# STM32FOC_AD_SCH.net
KiCad netlist of a schematic drawn in Altium Designer
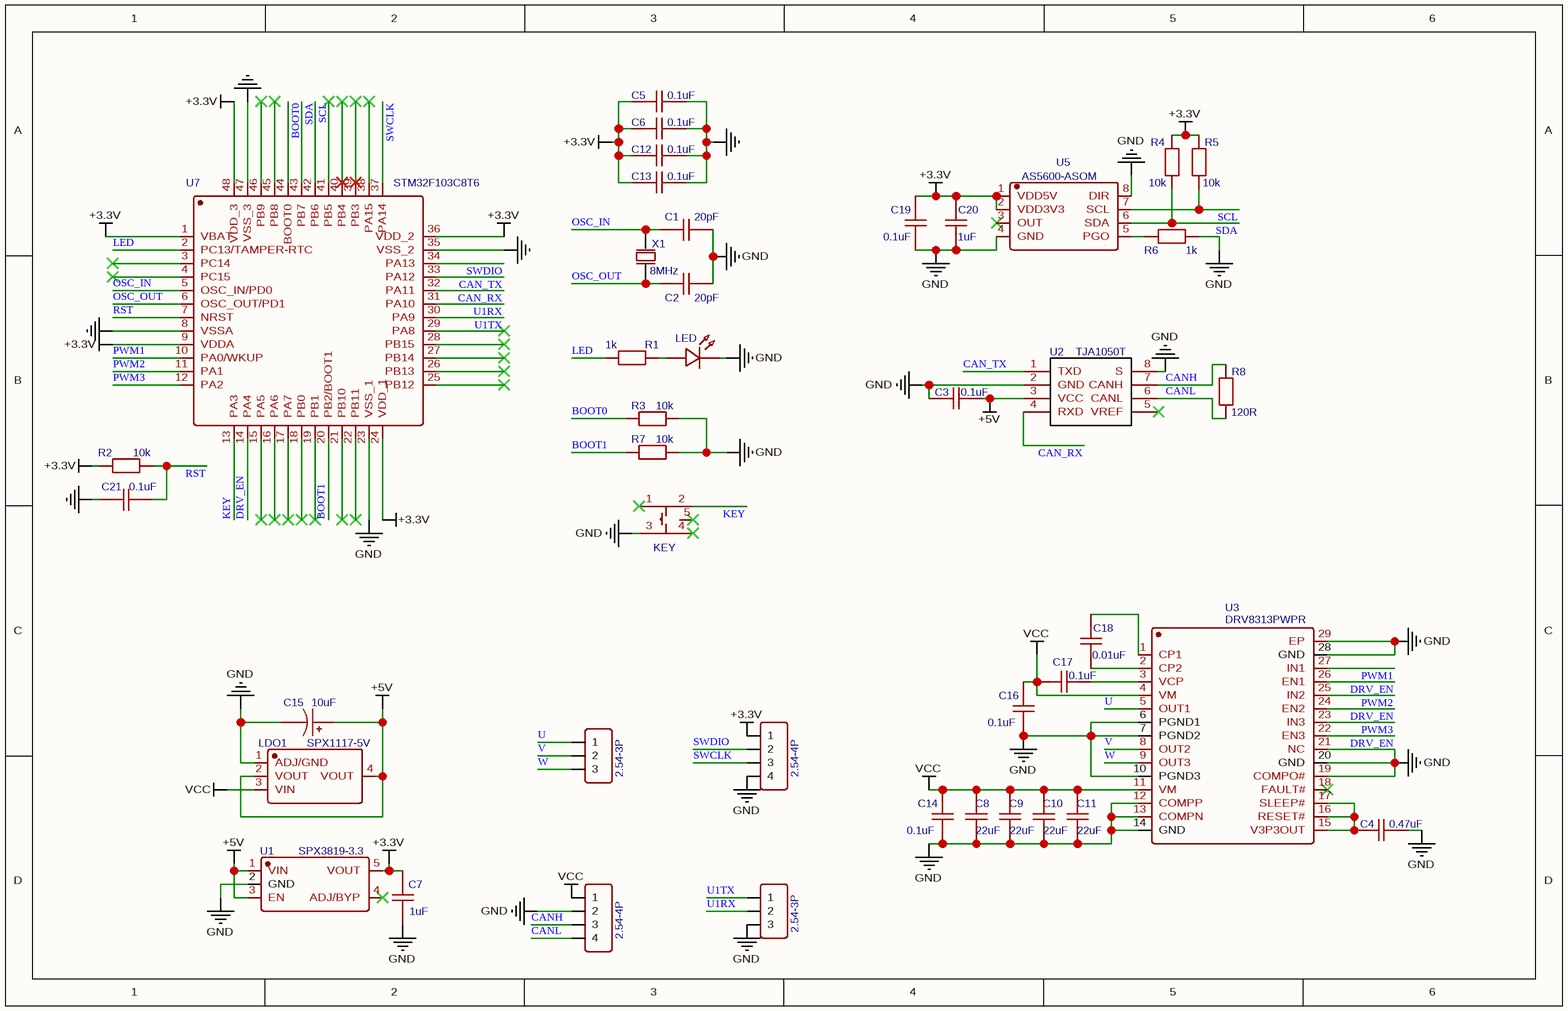
[diagram p0: STM32FOC_AD_SCH.schdoc]

(export (version "E")
  (design (tool "Eeschema 10.0.6"))
  (components
    (comp (ref "C1")
      (value "20pF")
      (fields (field (name "CONTRIBUTOR") "LCEDA_Lib"))
      (libsource (lib "altium-import") (part "root_0_20pF_"))
    )
    (comp (ref "C2")
      (value "20pF")
      (fields (field (name "CONTRIBUTOR") "LCEDA_Lib"))
      (libsource (lib "altium-import") (part "root_0_20pF_"))
    )
    (comp (ref "C3")
      (value "0.1uF")
      (fields (field (name "CONTRIBUTOR") "LCEDA_Lib"))
      (libsource (lib "altium-import") (part "root_0_0.1uF_"))
    )
    (comp (ref "C4")
      (value "0.47uF")
      (fields (field (name "CONTRIBUTOR") "LCEDA_Lib"))
      (libsource (lib "altium-import") (part "root_2_0.47uF_"))
    )
    (comp (ref "C5")
      (value "0.1uF")
      (fields (field (name "CONTRIBUTOR") "LCEDA_Lib"))
      (libsource (lib "altium-import") (part "root_0_0.1uF_"))
    )
    (comp (ref "C6")
      (value "0.1uF")
      (fields (field (name "CONTRIBUTOR") "LCEDA_Lib"))
      (libsource (lib "altium-import") (part "root_0_0.1uF_"))
    )
    (comp (ref "C7")
      (value "1uF")
      (fields (field (name "CONTRIBUTOR") "LCEDA_Lib"))
      (libsource (lib "altium-import") (part "root_1_1uF_"))
    )
    (comp (ref "C8")
      (value "22uF")
      (fields (field (name "CONTRIBUTOR") "LCEDA_Lib"))
      (libsource (lib "altium-import") (part "root_1_22uF_"))
    )
    (comp (ref "C9")
      (value "22uF")
      (fields (field (name "CONTRIBUTOR") "LCEDA_Lib"))
      (libsource (lib "altium-import") (part "root_1_22uF_"))
    )
    (comp (ref "C10")
      (value "22uF")
      (fields (field (name "CONTRIBUTOR") "LCEDA_Lib"))
      (libsource (lib "altium-import") (part "root_1_22uF_"))
    )
    (comp (ref "C11")
      (value "22uF")
      (fields (field (name "CONTRIBUTOR") "LCEDA_Lib"))
      (libsource (lib "altium-import") (part "root_1_22uF_"))
    )
    (comp (ref "C12")
      (value "0.1uF")
      (fields (field (name "CONTRIBUTOR") "LCEDA_Lib"))
      (libsource (lib "altium-import") (part "root_0_0.1uF_"))
    )
    (comp (ref "C13")
      (value "0.1uF")
      (fields (field (name "CONTRIBUTOR") "LCEDA_Lib"))
      (libsource (lib "altium-import") (part "root_0_0.1uF_"))
    )
    (comp (ref "C14")
      (value "0.1uF")
      (fields (field (name "CONTRIBUTOR") "LCEDA_Lib"))
      (libsource (lib "altium-import") (part "root_1_0.1uF_"))
    )
    (comp (ref "C15")
      (value "10uF")
      (fields (field (name "CONTRIBUTOR") "LCEDA_Lib"))
      (libsource (lib "altium-import") (part "root_2_10uF_"))
    )
    (comp (ref "C16")
      (value "0.1uF")
      (fields (field (name "CONTRIBUTOR") "LCEDA_Lib"))
      (libsource (lib "altium-import") (part "root_1_0.1uF_"))
    )
    (comp (ref "C17")
      (value "0.1uF")
      (fields (field (name "CONTRIBUTOR") "LCEDA_Lib"))
      (libsource (lib "altium-import") (part "root_2_0.1uF_"))
    )
    (comp (ref "C18")
      (value "0.01uF")
      (fields (field (name "CONTRIBUTOR") "LCEDA_Lib"))
      (libsource (lib "altium-import") (part "root_1_0.01uF_"))
    )
    (comp (ref "C19")
      (value "0.1uF")
      (fields (field (name "CONTRIBUTOR") "LCEDA_Lib"))
      (libsource (lib "altium-import") (part "root_1_0.1uF_"))
    )
    (comp (ref "C20")
      (value "1uF")
      (fields (field (name "CONTRIBUTOR") "LCEDA_Lib"))
      (libsource (lib "altium-import") (part "root_1_1uF_"))
    )
    (comp (ref "C21")
      (value "0.1uF")
      (fields (field (name "CONTRIBUTOR") "LCEDA_Lib"))
      (libsource (lib "altium-import") (part "root_0_0.1uF_"))
    )
    (comp (ref "J1")
      (value "2.54-4P")
      (fields (field (name "BOM_SUPPLIER PART") "C124378") (field (name "CONTRIBUTOR") "LCEDA_Lib"))
      (libsource (lib "altium-import") (part "root_0_2.54-4P_"))
    )
    (comp (ref "J2")
      (value "2.54-3P")
      (fields (field (name "BOM_SUPPLIER PART") "C180248") (field (name "CONTRIBUTOR") "LCEDA_Lib"))
      (libsource (lib "altium-import") (part "root_0_2.54-3P_"))
    )
    (comp (ref "J3")
      (value "2.54-3P")
      (fields (field (name "BOM_SUPPLIER PART") "C180248") (field (name "CONTRIBUTOR") "LCEDA_Lib"))
      (libsource (lib "altium-import") (part "root_0_2.54-3P_"))
    )
    (comp (ref "J4")
      (value "2.54-4P")
      (fields (field (name "BOM_SUPPLIER PART") "C124378") (field (name "CONTRIBUTOR") "LCEDA_Lib"))
      (libsource (lib "altium-import") (part "root_0_2.54-4P_"))
    )
    (comp (ref "KEY")
      (value "YTSA007A0152501B")
      (fields (field (name "BOM_SUPPLIER PART") "C967768") (field (name "CONTRIBUTOR") "LCSC"))
      (libsource (lib "altium-import") (part "root_0_YTSA007A0152501B_"))
    )
    (comp (ref "LDO1")
      (value "SPX1117-5V")
      (fields
        (field (name "BOM_MANUFACTURER PART") "SPX1117M3-L/TR")
        (field (name "BOM_SUPPLIER PART") "C67402")
      )
      (libsource (lib "altium-import") (part "root_0_SPX1117-5V_"))
    )
    (comp (ref "LED")
      (value "LED-0603_R")
      (fields
        (field (name "BOM_MANUFACTURER PART") "19-217/R6C-AL1M2VY/3T")
        (field (name "BOM_SUPPLIER PART") "C72044")
        (field (name "CONTRIBUTOR") "LCEDA_01")
      )
      (libsource (lib "altium-import") (part "root_2_LED-0603_R_"))
    )
    (comp (ref "R1")
      (value "1k")
      (fields (field (name "CONTRIBUTOR") "LCEDA_Lib"))
      (libsource (lib "") (part "root_0_1k__1"))
    )
    (comp (ref "R2")
      (value "10k")
      (fields (field (name "CONTRIBUTOR") "LCEDA_Lib"))
      (libsource (lib "altium-import") (part "root_0_10k_"))
    )
    (comp (ref "R3")
      (value "10k")
      (fields (field (name "CONTRIBUTOR") "LCEDA_Lib"))
      (libsource (lib "altium-import") (part "root_0_10k_"))
    )
    (comp (ref "R4")
      (value "10k")
      (fields (field (name "CONTRIBUTOR") "LCEDA_Lib"))
      (libsource (lib "altium-import") (part "root_1_10k_"))
    )
    (comp (ref "R5")
      (value "10k")
      (fields (field (name "CONTRIBUTOR") "LCEDA_Lib"))
      (libsource (lib "altium-import") (part "root_1_10k_"))
    )
    (comp (ref "R6")
      (value "1k")
      (fields (field (name "CONTRIBUTOR") "LCEDA_Lib"))
      (libsource (lib "altium-import") (part "root_0_1k_"))
    )
    (comp (ref "R7")
      (value "10k")
      (fields (field (name "CONTRIBUTOR") "LCEDA_Lib"))
      (libsource (lib "altium-import") (part "root_2_10k_"))
    )
    (comp (ref "R8")
      (value "120R")
      (fields (field (name "CONTRIBUTOR") "LCEDA_Lib"))
      (libsource (lib "altium-import") (part "root_1_120R_"))
    )
    (comp (ref "U1")
      (value "SPX3819-3.3")
      (fields
        (field (name "BOM_SUPPLIER PART") "C9900018941")
        (field (name "BOM_MANUFACTURER PART") "SPX3819M5-3.3")
        (field (name "CONTRIBUTOR") "lcsc")
      )
      (libsource (lib "altium-import") (part "root_0_SPX3819-3.3_"))
    )
    (comp (ref "U2")
      (value "TJA1050T")
      (fields
        (field (name "BOM_MANUFACTURER PART") "TJA1050T/CM,118")
        (field (name "BOM_SUPPLIER PART") "C6952")
      )
      (libsource (lib "altium-import") (part "root_0_TJA1050T_"))
    )
    (comp (ref "U3")
      (value "DRV8313PWPR")
      (fields (field (name "BOM_SUPPLIER PART") "C92482") (field (name "CONTRIBUTOR") "LCSC"))
      (libsource (lib "altium-import") (part "root_0_DRV8313PWPR_"))
    )
    (comp (ref "U5")
      (value "AS5600-ASOM")
      (fields (field (name "BOM_SUPPLIER PART") "C79815"))
      (libsource (lib "altium-import") (part "root_0_AS5600-ASOM_"))
    )
    (comp (ref "U7")
      (value "STM32F103C8T6")
      (fields (field (name "BOM_MANUFACTURER PART") "?"))
      (libsource (lib "altium-import") (part "root_0_STM32F103C8T6_"))
    )
    (comp (ref "X1")
      (value "8MHz")
      (fields
        (field (name "BOM_MANUFACTURER PART") "X50328MSB2GI")
        (field (name "BOM_SUPPLIER PART") "C115962")
      )
      (libsource (lib "altium-import") (part "root_1_8MHz_"))
    )
  )
  (nets
    (net (code "1") (name "+3.3V") (class "Default")
      (node (ref "C12") (pin "1") (pinfunction "1_1") (pintype "passive"))
      (node (ref "C13") (pin "1") (pinfunction "1_1") (pintype "passive"))
      (node (ref "C19") (pin "2") (pinfunction "2_2") (pintype "passive"))
      (node (ref "C20") (pin "2") (pinfunction "2_2") (pintype "passive"))
      (node (ref "C5") (pin "1") (pinfunction "1_1") (pintype "passive"))
      (node (ref "C6") (pin "1") (pinfunction "1_1") (pintype "passive"))
      (node (ref "C7") (pin "2") (pinfunction "2_2") (pintype "passive"))
      (node (ref "J1") (pin "1") (pinfunction "1_1") (pintype "passive"))
      (node (ref "R2") (pin "1") (pinfunction "1_1") (pintype "passive"))
      (node (ref "R4") (pin "2") (pinfunction "2_2") (pintype "passive"))
      (node (ref "R5") (pin "2") (pinfunction "2_2") (pintype "passive"))
      (node (ref "U1") (pin "5") (pinfunction "VOUT_5") (pintype "passive"))
      (node (ref "U5") (pin "1") (pinfunction "VDD5V_1") (pintype "passive"))
      (node (ref "U5") (pin "2") (pinfunction "VDD3V3_2") (pintype "passive"))
      (node (ref "U7") (pin "1") (pinfunction "VBAT_1") (pintype "passive"))
      (node (ref "U7") (pin "24") (pinfunction "VDD_1_24") (pintype "passive"))
      (node (ref "U7") (pin "36") (pinfunction "VDD_2_36") (pintype "passive"))
      (node (ref "U7") (pin "48") (pinfunction "VDD_3_48") (pintype "passive"))
      (node (ref "U7") (pin "9") (pinfunction "VDDA_9") (pintype "passive"))
    )
    (net (code "2") (name "+5V") (class "Default")
      (node (ref "C15") (pin "1") (pinfunction "1_1") (pintype "passive"))
      (node (ref "C3") (pin "2") (pinfunction "2_2") (pintype "passive"))
      (node (ref "LDO1") (pin "2") (pinfunction "VOUT_2") (pintype "passive"))
      (node (ref "LDO1") (pin "4") (pinfunction "VOUT_4") (pintype "passive"))
      (node (ref "U1") (pin "1") (pinfunction "VIN_1") (pintype "passive"))
      (node (ref "U1") (pin "3") (pinfunction "EN_3") (pintype "passive"))
      (node (ref "U2") (pin "3") (pinfunction "VCC_3") (pintype "passive"))
    )
    (net (code "3") (name "/BOOT0") (class "Default")
      (node (ref "R3") (pin "1") (pinfunction "1_1") (pintype "passive"))
      (node (ref "U7") (pin "44") (pinfunction "BOOT0_44") (pintype "passive"))
    )
    (net (code "4") (name "/BOOT1") (class "Default")
      (node (ref "R7") (pin "2") (pinfunction "2_2") (pintype "passive"))
      (node (ref "U7") (pin "20") (pinfunction "PB2/BOOT1_20") (pintype "passive"))
    )
    (net (code "5") (name "/CANH") (class "Default")
      (node (ref "J4") (pin "3") (pinfunction "3_3") (pintype "passive"))
      (node (ref "R8") (pin "2") (pinfunction "2_2") (pintype "passive"))
      (node (ref "U2") (pin "7") (pinfunction "CANH_7") (pintype "passive"))
    )
    (net (code "6") (name "/CANL") (class "Default")
      (node (ref "J4") (pin "4") (pinfunction "4_4") (pintype "passive"))
      (node (ref "R8") (pin "1") (pinfunction "1_1") (pintype "passive"))
      (node (ref "U2") (pin "6") (pinfunction "CANL_6") (pintype "passive"))
    )
    (net (code "7") (name "/CAN_RX") (class "Default")
      (node (ref "U2") (pin "4") (pinfunction "RXD_4") (pintype "passive"))
      (node (ref "U7") (pin "32") (pinfunction "PA11_32") (pintype "passive"))
    )
    (net (code "8") (name "/CAN_TX") (class "Default")
      (node (ref "U2") (pin "1") (pinfunction "TXD_1") (pintype "passive"))
      (node (ref "U7") (pin "33") (pinfunction "PA12_33") (pintype "passive"))
    )
    (net (code "9") (name "/DRV_EN") (class "Default")
      (node (ref "U3") (pin "22") (pinfunction "EN3_22") (pintype "passive"))
      (node (ref "U3") (pin "24") (pinfunction "EN2_24") (pintype "passive"))
      (node (ref "U3") (pin "26") (pinfunction "EN1_26") (pintype "passive"))
      (node (ref "U7") (pin "14") (pinfunction "PA4_14") (pintype "passive"))
    )
    (net (code "10") (name "/KEY") (class "Default")
      (node (ref "KEY") (pin "2") (pinfunction "2_2") (pintype "passive"))
      (node (ref "U7") (pin "13") (pinfunction "PA3_13") (pintype "passive"))
    )
    (net (code "11") (name "/LED") (class "Default")
      (node (ref "R1") (pin "2") (pinfunction "2_2") (pintype "passive"))
      (node (ref "U7") (pin "2") (pinfunction "PC13/TAMPER-RTC_2") (pintype "passive"))
    )
    (net (code "12") (name "/OSC_IN") (class "Default")
      (node (ref "C1") (pin "1") (pinfunction "1_1") (pintype "passive"))
      (node (ref "U7") (pin "5") (pinfunction "OSC_IN/PD0_5") (pintype "passive"))
      (node (ref "X1") (pin "2") (pinfunction "OSC2_2") (pintype "passive"))
    )
    (net (code "13") (name "/OSC_OUT") (class "Default")
      (node (ref "C2") (pin "1") (pinfunction "1_1") (pintype "passive"))
      (node (ref "U7") (pin "6") (pinfunction "OSC_OUT/PD1_6") (pintype "passive"))
      (node (ref "X1") (pin "1") (pinfunction "OSC1_1") (pintype "passive"))
    )
    (net (code "14") (name "/PWM1") (class "Default")
      (node (ref "U3") (pin "27") (pinfunction "IN1_27") (pintype "passive"))
      (node (ref "U7") (pin "10") (pinfunction "PA0/WKUP_10") (pintype "passive"))
    )
    (net (code "15") (name "/PWM2") (class "Default")
      (node (ref "U3") (pin "25") (pinfunction "IN2_25") (pintype "passive"))
      (node (ref "U7") (pin "11") (pinfunction "PA1_11") (pintype "passive"))
    )
    (net (code "16") (name "/PWM3") (class "Default")
      (node (ref "U3") (pin "23") (pinfunction "IN3_23") (pintype "passive"))
      (node (ref "U7") (pin "12") (pinfunction "PA2_12") (pintype "passive"))
    )
    (net (code "17") (name "/RST") (class "Default")
      (node (ref "C21") (pin "2") (pinfunction "2_2") (pintype "passive"))
      (node (ref "R2") (pin "2") (pinfunction "2_2") (pintype "passive"))
      (node (ref "U7") (pin "7") (pinfunction "NRST_7") (pintype "passive"))
    )
    (net (code "18") (name "/SCL") (class "Default")
      (node (ref "R5") (pin "1") (pinfunction "1_1") (pintype "passive"))
      (node (ref "U5") (pin "7") (pinfunction "SCL_7") (pintype "passive"))
      (node (ref "U7") (pin "42") (pinfunction "PB6_42") (pintype "passive"))
    )
    (net (code "19") (name "/SDA") (class "Default")
      (node (ref "R4") (pin "1") (pinfunction "1_1") (pintype "passive"))
      (node (ref "U5") (pin "6") (pinfunction "SDA_6") (pintype "passive"))
      (node (ref "U7") (pin "43") (pinfunction "PB7_43") (pintype "passive"))
    )
    (net (code "20") (name "/SWCLK") (class "Default")
      (node (ref "J1") (pin "3") (pinfunction "3_3") (pintype "passive"))
      (node (ref "U7") (pin "37") (pinfunction "PA14_37") (pintype "passive"))
    )
    (net (code "21") (name "/SWDIO") (class "Default")
      (node (ref "J1") (pin "2") (pinfunction "2_2") (pintype "passive"))
      (node (ref "U7") (pin "34") (pinfunction "PA13_34") (pintype "passive"))
    )
    (net (code "22") (name "/U") (class "Default")
      (node (ref "J3") (pin "1") (pinfunction "1_1") (pintype "passive"))
      (node (ref "U3") (pin "5") (pinfunction "OUT1_5") (pintype "passive"))
    )
    (net (code "23") (name "/U1RX") (class "Default")
      (node (ref "J2") (pin "2") (pinfunction "2_2") (pintype "passive"))
      (node (ref "U7") (pin "31") (pinfunction "PA10_31") (pintype "passive"))
    )
    (net (code "24") (name "/U1TX") (class "Default")
      (node (ref "J2") (pin "1") (pinfunction "1_1") (pintype "passive"))
      (node (ref "U7") (pin "30") (pinfunction "PA9_30") (pintype "passive"))
    )
    (net (code "25") (name "/V") (class "Default")
      (node (ref "J3") (pin "2") (pinfunction "2_2") (pintype "passive"))
      (node (ref "U3") (pin "8") (pinfunction "OUT2_8") (pintype "passive"))
    )
    (net (code "26") (name "/W") (class "Default")
      (node (ref "J3") (pin "3") (pinfunction "3_3") (pintype "passive"))
      (node (ref "U3") (pin "9") (pinfunction "OUT3_9") (pintype "passive"))
    )
    (net (code "27") (name "GND") (class "Default")
      (node (ref "C1") (pin "2") (pinfunction "2_2") (pintype "passive"))
      (node (ref "C10") (pin "1") (pinfunction "1_1") (pintype "passive"))
      (node (ref "C11") (pin "1") (pinfunction "1_1") (pintype "passive"))
      (node (ref "C12") (pin "2") (pinfunction "2_2") (pintype "passive"))
      (node (ref "C13") (pin "2") (pinfunction "2_2") (pintype "passive"))
      (node (ref "C14") (pin "1") (pinfunction "1_1") (pintype "passive"))
      (node (ref "C15") (pin "2") (pinfunction "2_2") (pintype "passive"))
      (node (ref "C16") (pin "1") (pinfunction "1_1") (pintype "passive"))
      (node (ref "C19") (pin "1") (pinfunction "1_1") (pintype "passive"))
      (node (ref "C2") (pin "2") (pinfunction "2_2") (pintype "passive"))
      (node (ref "C20") (pin "1") (pinfunction "1_1") (pintype "passive"))
      (node (ref "C21") (pin "1") (pinfunction "1_1") (pintype "passive"))
      (node (ref "C3") (pin "1") (pinfunction "1_1") (pintype "passive"))
      (node (ref "C4") (pin "1") (pinfunction "1_1") (pintype "passive"))
      (node (ref "C5") (pin "2") (pinfunction "2_2") (pintype "passive"))
      (node (ref "C6") (pin "2") (pinfunction "2_2") (pintype "passive"))
      (node (ref "C7") (pin "1") (pinfunction "1_1") (pintype "passive"))
      (node (ref "C8") (pin "1") (pinfunction "1_1") (pintype "passive"))
      (node (ref "C9") (pin "1") (pinfunction "1_1") (pintype "passive"))
      (node (ref "J1") (pin "4") (pinfunction "4_4") (pintype "passive"))
      (node (ref "J2") (pin "3") (pinfunction "3_3") (pintype "passive"))
      (node (ref "J4") (pin "2") (pinfunction "2_2") (pintype "passive"))
      (node (ref "KEY") (pin "3") (pinfunction "3_3") (pintype "passive"))
      (node (ref "LDO1") (pin "1") (pinfunction "ADJ/GND_1") (pintype "passive"))
      (node (ref "LED") (pin "2") (pinfunction "2_2") (pintype "passive"))
      (node (ref "R3") (pin "2") (pinfunction "2_2") (pintype "passive"))
      (node (ref "R6") (pin "2") (pinfunction "2_2") (pintype "passive"))
      (node (ref "R7") (pin "1") (pinfunction "1_1") (pintype "passive"))
      (node (ref "U1") (pin "2") (pinfunction "GND_2") (pintype "passive"))
      (node (ref "U2") (pin "2") (pinfunction "GND_2") (pintype "passive"))
      (node (ref "U2") (pin "8") (pinfunction "S_8") (pintype "passive"))
      (node (ref "U3") (pin "10") (pinfunction "PGND3_10") (pintype "passive"))
      (node (ref "U3") (pin "12") (pinfunction "COMPP_12") (pintype "passive"))
      (node (ref "U3") (pin "13") (pinfunction "COMPN_13") (pintype "passive"))
      (node (ref "U3") (pin "14") (pinfunction "GND_14") (pintype "passive"))
      (node (ref "U3") (pin "19") (pinfunction "COMPO#_19") (pintype "passive"))
      (node (ref "U3") (pin "20") (pinfunction "GND_20") (pintype "passive"))
      (node (ref "U3") (pin "21") (pinfunction "NC_21") (pintype "passive"))
      (node (ref "U3") (pin "28") (pinfunction "GND_28") (pintype "passive"))
      (node (ref "U3") (pin "29") (pinfunction "EP_29") (pintype "passive"))
      (node (ref "U3") (pin "6") (pinfunction "PGND1_6") (pintype "passive"))
      (node (ref "U3") (pin "7") (pinfunction "PGND2_7") (pintype "passive"))
      (node (ref "U5") (pin "4") (pinfunction "GND_4") (pintype "passive"))
      (node (ref "U5") (pin "8") (pinfunction "DIR_8") (pintype "passive"))
      (node (ref "U7") (pin "23") (pinfunction "VSS_1_23") (pintype "passive"))
      (node (ref "U7") (pin "35") (pinfunction "VSS_2_35") (pintype "passive"))
      (node (ref "U7") (pin "47") (pinfunction "VSS_3_47") (pintype "passive"))
      (node (ref "U7") (pin "8") (pinfunction "VSSA_8") (pintype "passive"))
    )
    (net (code "28") (name "Net-(LED-Pad1)") (class "Default")
      (node (ref "LED") (pin "1") (pinfunction "1_1") (pintype "passive"))
      (node (ref "R1") (pin "1") (pinfunction "1_1") (pintype "passive"))
    )
    (net (code "29") (name "Net-(U3-CP1)") (class "Default")
      (node (ref "C18") (pin "2") (pinfunction "2_2") (pintype "passive"))
      (node (ref "U3") (pin "1") (pinfunction "CP1_1") (pintype "passive"))
    )
    (net (code "30") (name "Net-(U3-CP2)") (class "Default")
      (node (ref "C18") (pin "1") (pinfunction "1_1") (pintype "passive"))
      (node (ref "U3") (pin "2") (pinfunction "CP2_2") (pintype "passive"))
    )
    (net (code "31") (name "Net-(U3-RESET#)") (class "Default")
      (node (ref "C4") (pin "2") (pinfunction "2_2") (pintype "passive"))
      (node (ref "U3") (pin "15") (pinfunction "V3P3OUT_15") (pintype "passive"))
      (node (ref "U3") (pin "16") (pinfunction "RESET#_16") (pintype "passive"))
      (node (ref "U3") (pin "17") (pinfunction "SLEEP#_17") (pintype "passive"))
    )
    (net (code "32") (name "Net-(U3-VCP)") (class "Default")
      (node (ref "C17") (pin "1") (pinfunction "1_1") (pintype "passive"))
      (node (ref "U3") (pin "3") (pinfunction "VCP_3") (pintype "passive"))
    )
    (net (code "33") (name "Net-(U5-PGO)") (class "Default")
      (node (ref "R6") (pin "1") (pinfunction "1_1") (pintype "passive"))
      (node (ref "U5") (pin "5") (pinfunction "PGO_5") (pintype "passive"))
    )
    (net (code "34") (name "VCC") (class "Default")
      (node (ref "C10") (pin "2") (pinfunction "2_2") (pintype "passive"))
      (node (ref "C11") (pin "2") (pinfunction "2_2") (pintype "passive"))
      (node (ref "C14") (pin "2") (pinfunction "2_2") (pintype "passive"))
      (node (ref "C16") (pin "2") (pinfunction "2_2") (pintype "passive"))
      (node (ref "C17") (pin "2") (pinfunction "2_2") (pintype "passive"))
      (node (ref "C8") (pin "2") (pinfunction "2_2") (pintype "passive"))
      (node (ref "C9") (pin "2") (pinfunction "2_2") (pintype "passive"))
      (node (ref "J4") (pin "1") (pinfunction "1_1") (pintype "passive"))
      (node (ref "LDO1") (pin "3") (pinfunction "VIN_3") (pintype "passive"))
      (node (ref "U3") (pin "11") (pinfunction "VM_11") (pintype "passive"))
      (node (ref "U3") (pin "4") (pinfunction "VM_4") (pintype "passive"))
    )
    (net (code "35") (name "unconnected-(KEY-Pad1)") (class "Default")
      (node (ref "KEY") (pin "1") (pinfunction "1_1") (pintype "passive+no_connect"))
    )
    (net (code "36") (name "unconnected-(KEY-Pad4)") (class "Default")
      (node (ref "KEY") (pin "4") (pinfunction "4_4") (pintype "passive+no_connect"))
    )
    (net (code "37") (name "unconnected-(KEY-Pad5)") (class "Default")
      (node (ref "KEY") (pin "5") (pinfunction "5_5") (pintype "passive+no_connect"))
    )
    (net (code "38") (name "unconnected-(U1-ADJ{slash}BYP-Pad4)") (class "Default")
      (node (ref "U1") (pin "4") (pinfunction "ADJ/BYP_4") (pintype "passive+no_connect"))
    )
    (net (code "39") (name "unconnected-(U2-VREF-Pad5)") (class "Default")
      (node (ref "U2") (pin "5") (pinfunction "VREF_5") (pintype "passive+no_connect"))
    )
    (net (code "40") (name "unconnected-(U3-FAULT#-Pad18)") (class "Default")
      (node (ref "U3") (pin "18") (pinfunction "FAULT#_18") (pintype "passive+no_connect"))
    )
    (net (code "41") (name "unconnected-(U5-OUT-Pad3)") (class "Default")
      (node (ref "U5") (pin "3") (pinfunction "OUT_3") (pintype "passive+no_connect"))
    )
    (net (code "42") (name "unconnected-(U7-PA5-Pad15)") (class "Default")
      (node (ref "U7") (pin "15") (pinfunction "PA5_15") (pintype "passive+no_connect"))
    )
    (net (code "43") (name "unconnected-(U7-PA6-Pad16)") (class "Default")
      (node (ref "U7") (pin "16") (pinfunction "PA6_16") (pintype "passive+no_connect"))
    )
    (net (code "44") (name "unconnected-(U7-PA7-Pad17)") (class "Default")
      (node (ref "U7") (pin "17") (pinfunction "PA7_17") (pintype "passive+no_connect"))
    )
    (net (code "45") (name "unconnected-(U7-PA8-Pad29)") (class "Default")
      (node (ref "U7") (pin "29") (pinfunction "PA8_29") (pintype "passive+no_connect"))
    )
    (net (code "46") (name "unconnected-(U7-PA15-Pad38)") (class "Default")
      (node (ref "U7") (pin "38") (pinfunction "PA15_38") (pintype "passive+no_connect"))
    )
    (net (code "47") (name "unconnected-(U7-PB0-Pad18)") (class "Default")
      (node (ref "U7") (pin "18") (pinfunction "PB0_18") (pintype "passive+no_connect"))
    )
    (net (code "48") (name "unconnected-(U7-PB1-Pad19)") (class "Default")
      (node (ref "U7") (pin "19") (pinfunction "PB1_19") (pintype "passive+no_connect"))
    )
    (net (code "49") (name "unconnected-(U7-PB3-Pad39)") (class "Default")
      (node (ref "U7") (pin "39") (pinfunction "PB3_39") (pintype "passive+no_connect"))
    )
    (net (code "50") (name "unconnected-(U7-PB4-Pad40)") (class "Default")
      (node (ref "U7") (pin "40") (pinfunction "PB4_40") (pintype "passive+no_connect"))
    )
    (net (code "51") (name "unconnected-(U7-PB5-Pad41)") (class "Default")
      (node (ref "U7") (pin "41") (pinfunction "PB5_41") (pintype "passive+no_connect"))
    )
    (net (code "52") (name "unconnected-(U7-PB8-Pad45)") (class "Default")
      (node (ref "U7") (pin "45") (pinfunction "PB8_45") (pintype "passive+no_connect"))
    )
    (net (code "53") (name "unconnected-(U7-PB9-Pad46)") (class "Default")
      (node (ref "U7") (pin "46") (pinfunction "PB9_46") (pintype "passive+no_connect"))
    )
    (net (code "54") (name "unconnected-(U7-PB10-Pad21)") (class "Default")
      (node (ref "U7") (pin "21") (pinfunction "PB10_21") (pintype "passive+no_connect"))
    )
    (net (code "55") (name "unconnected-(U7-PB11-Pad22)") (class "Default")
      (node (ref "U7") (pin "22") (pinfunction "PB11_22") (pintype "passive+no_connect"))
    )
    (net (code "56") (name "unconnected-(U7-PB12-Pad25)") (class "Default")
      (node (ref "U7") (pin "25") (pinfunction "PB12_25") (pintype "passive+no_connect"))
    )
    (net (code "57") (name "unconnected-(U7-PB13-Pad26)") (class "Default")
      (node (ref "U7") (pin "26") (pinfunction "PB13_26") (pintype "passive+no_connect"))
    )
    (net (code "58") (name "unconnected-(U7-PB14-Pad27)") (class "Default")
      (node (ref "U7") (pin "27") (pinfunction "PB14_27") (pintype "passive+no_connect"))
    )
    (net (code "59") (name "unconnected-(U7-PB15-Pad28)") (class "Default")
      (node (ref "U7") (pin "28") (pinfunction "PB15_28") (pintype "passive+no_connect"))
    )
    (net (code "60") (name "unconnected-(U7-PC14-Pad3)") (class "Default")
      (node (ref "U7") (pin "3") (pinfunction "PC14_3") (pintype "passive+no_connect"))
    )
    (net (code "61") (name "unconnected-(U7-PC15-Pad4)") (class "Default")
      (node (ref "U7") (pin "4") (pinfunction "PC15_4") (pintype "passive+no_connect"))
    )
  )
)
